# usbhub.net
KiCad netlist of a schematic drawn in EAGLE
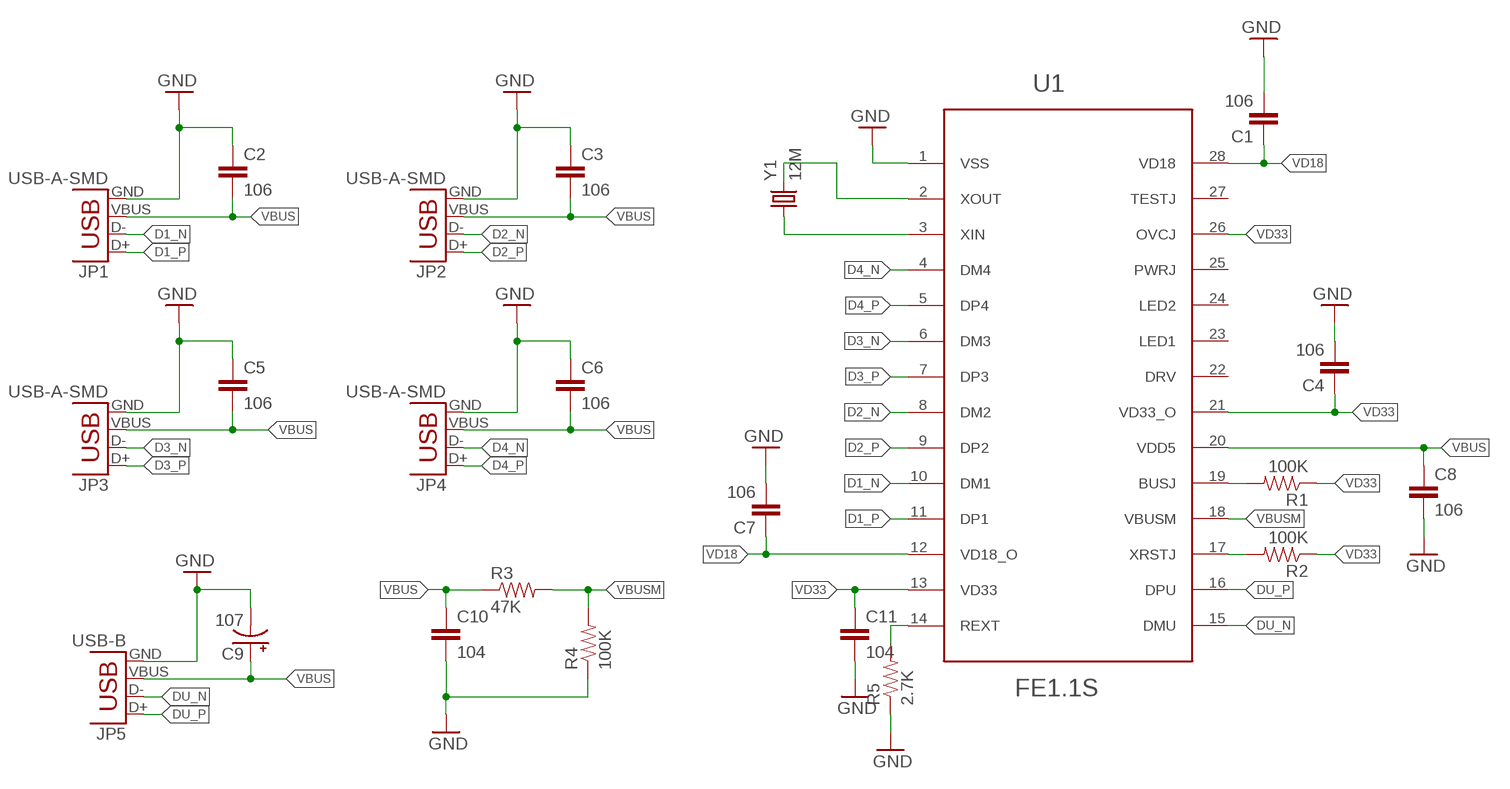
[diagram p0: schematic, sheet 1]

(export (version "E")
  (design (tool "Eeschema 10.0.6"))
  (components
    (comp (ref "C1")
      (value "106")
      (footprint "eagle-import:0603-CAP")
      (libsource (lib "eagle-import") (part "CAP0603-CAP"))
    )
    (comp (ref "C2")
      (value "106")
      (footprint "eagle-import:0603-CAP")
      (libsource (lib "eagle-import") (part "z_jlc_smt_CAP0603-CAP"))
    )
    (comp (ref "C3")
      (value "106")
      (footprint "eagle-import:0603-CAP")
      (libsource (lib "eagle-import") (part "z_jlc_smt_CAP0603-CAP"))
    )
    (comp (ref "C4")
      (value "106")
      (footprint "eagle-import:0603-CAP")
      (libsource (lib "eagle-import") (part "CAP0603-CAP"))
    )
    (comp (ref "C5")
      (value "106")
      (footprint "eagle-import:0603-CAP")
      (libsource (lib "eagle-import") (part "z_jlc_smt_CAP0603-CAP"))
    )
    (comp (ref "C6")
      (value "106")
      (footprint "eagle-import:0603-CAP")
      (libsource (lib "eagle-import") (part "z_jlc_smt_CAP0603-CAP"))
    )
    (comp (ref "C7")
      (value "106")
      (footprint "eagle-import:0603-CAP")
      (libsource (lib "eagle-import") (part "CAP0603-CAP"))
    )
    (comp (ref "C8")
      (value "106")
      (footprint "eagle-import:0603-CAP")
      (libsource (lib "eagle-import") (part "CAP0603-CAP"))
    )
    (comp (ref "C9")
      (value "107")
      (footprint "eagle-import:EIA3528-KIT")
      (libsource (lib "eagle-import") (part "CAP_POL3528-KIT"))
    )
    (comp (ref "C10")
      (value "104")
      (footprint "eagle-import:0603-CAP")
      (libsource (lib "eagle-import") (part "z_jlc_smt_CAP0603-CAP"))
    )
    (comp (ref "C11")
      (value "104")
      (footprint "eagle-import:0603-CAP")
      (libsource (lib "eagle-import") (part "CAP0603-CAP"))
    )
    (comp (ref "JP1")
      (value "USB-A-SMD")
      (footprint "eagle-import:USB-A-S-NOSILK-FEMALE")
      (libsource (lib "eagle-import") (part "USB-A-SMD"))
    )
    (comp (ref "JP2")
      (value "USB-A-SMD")
      (footprint "eagle-import:USB-A-S-NOSILK-FEMALE")
      (libsource (lib "eagle-import") (part "USB-A-SMD"))
    )
    (comp (ref "JP3")
      (value "USB-A-SMD")
      (footprint "eagle-import:USB-A-S-NOSILK-FEMALE")
      (libsource (lib "eagle-import") (part "USB-A-SMD"))
    )
    (comp (ref "JP4")
      (value "USB-A-SMD")
      (footprint "eagle-import:USB-A-S-NOSILK-FEMALE")
      (libsource (lib "eagle-import") (part "USB-A-SMD"))
    )
    (comp (ref "JP5")
      (value "USB-B")
      (footprint "eagle-import:USB-B-PTH")
      (libsource (lib "eagle-import") (part "USBPTH"))
    )
    (comp (ref "R1")
      (value "100K")
      (footprint "eagle-import:0603-RES")
      (libsource (lib "eagle-import") (part "RESISTOR0603-RES"))
    )
    (comp (ref "R2")
      (value "100K")
      (footprint "eagle-import:0603-RES")
      (libsource (lib "eagle-import") (part "RESISTOR0603-RES"))
    )
    (comp (ref "R3")
      (value "47K")
      (footprint "eagle-import:0603-RES")
      (libsource (lib "eagle-import") (part "RESISTOR0603-RES"))
    )
    (comp (ref "R4")
      (value "100K")
      (footprint "eagle-import:0603-RES")
      (libsource (lib "eagle-import") (part "RESISTOR0603-RES"))
    )
    (comp (ref "R5")
      (value "2.7K")
      (footprint "eagle-import:0603-RES")
      (libsource (lib "eagle-import") (part "RESISTOR0603-RES"))
    )
    (comp (ref "U1")
      (value "FE1.1S")
      (footprint "eagle-import:SSOP28-39")
      (libsource (lib "eagle-import") (part "FE1.1S"))
    )
    (comp (ref "Y1")
      (value "12M")
      (footprint "eagle-import:HC49US")
      (libsource (lib "eagle-import") (part "CRYSTAL2HC49US"))
    )
  )
  (nets
    (net (code "1") (name "D1_N") (class "Default")
      (node (ref "JP1") (pin "D-") (pinfunction "D-_D-") (pintype "bidirectional"))
      (node (ref "U1") (pin "10") (pinfunction "DM1_10") (pintype "bidirectional"))
    )
    (net (code "2") (name "D1_P") (class "Default")
      (node (ref "JP1") (pin "D+") (pinfunction "D+_D+") (pintype "bidirectional"))
      (node (ref "U1") (pin "11") (pinfunction "DP1_11") (pintype "bidirectional"))
    )
    (net (code "3") (name "D2_N") (class "Default")
      (node (ref "JP2") (pin "D-") (pinfunction "D-_D-") (pintype "bidirectional"))
      (node (ref "U1") (pin "8") (pinfunction "DM2_8") (pintype "bidirectional"))
    )
    (net (code "4") (name "D2_P") (class "Default")
      (node (ref "JP2") (pin "D+") (pinfunction "D+_D+") (pintype "bidirectional"))
      (node (ref "U1") (pin "9") (pinfunction "DP2_9") (pintype "bidirectional"))
    )
    (net (code "5") (name "D3_N") (class "Default")
      (node (ref "JP3") (pin "D-") (pinfunction "D-_D-") (pintype "bidirectional"))
      (node (ref "U1") (pin "6") (pinfunction "DM3_6") (pintype "bidirectional"))
    )
    (net (code "6") (name "D3_P") (class "Default")
      (node (ref "JP3") (pin "D+") (pinfunction "D+_D+") (pintype "bidirectional"))
      (node (ref "U1") (pin "7") (pinfunction "DP3_7") (pintype "bidirectional"))
    )
    (net (code "7") (name "D4_N") (class "Default")
      (node (ref "JP4") (pin "D-") (pinfunction "D-_D-") (pintype "bidirectional"))
      (node (ref "U1") (pin "4") (pinfunction "DM4_4") (pintype "bidirectional"))
    )
    (net (code "8") (name "D4_P") (class "Default")
      (node (ref "JP4") (pin "D+") (pinfunction "D+_D+") (pintype "bidirectional"))
      (node (ref "U1") (pin "5") (pinfunction "DP4_5") (pintype "bidirectional"))
    )
    (net (code "9") (name "DU_N") (class "Default")
      (node (ref "JP5") (pin "D-") (pinfunction "D-_D-") (pintype "bidirectional"))
      (node (ref "U1") (pin "15") (pinfunction "DMU_15") (pintype "bidirectional"))
    )
    (net (code "10") (name "DU_P") (class "Default")
      (node (ref "JP5") (pin "D+") (pinfunction "D+_D+") (pintype "bidirectional"))
      (node (ref "U1") (pin "16") (pinfunction "DPU_16") (pintype "bidirectional"))
    )
    (net (code "11") (name "GND") (class "Default")
      (node (ref "C1") (pin "2") (pinfunction "2_2") (pintype "passive"))
      (node (ref "C10") (pin "2") (pinfunction "2_2") (pintype "passive"))
      (node (ref "C11") (pin "2") (pinfunction "2_2") (pintype "passive"))
      (node (ref "C2") (pin "1") (pinfunction "1_1") (pintype "passive"))
      (node (ref "C3") (pin "1") (pinfunction "1_1") (pintype "passive"))
      (node (ref "C4") (pin "2") (pinfunction "2_2") (pintype "passive"))
      (node (ref "C5") (pin "1") (pinfunction "1_1") (pintype "passive"))
      (node (ref "C6") (pin "1") (pinfunction "1_1") (pintype "passive"))
      (node (ref "C7") (pin "2") (pinfunction "2_2") (pintype "passive"))
      (node (ref "C8") (pin "2") (pinfunction "2_2") (pintype "passive"))
      (node (ref "C9") (pin "C") (pinfunction "-_C") (pintype "passive"))
      (node (ref "JP1") (pin "GND") (pinfunction "GND_GND") (pintype "bidirectional"))
      (node (ref "JP2") (pin "GND") (pinfunction "GND_GND") (pintype "bidirectional"))
      (node (ref "JP3") (pin "GND") (pinfunction "GND_GND") (pintype "bidirectional"))
      (node (ref "JP4") (pin "GND") (pinfunction "GND_GND") (pintype "bidirectional"))
      (node (ref "JP5") (pin "GND") (pinfunction "GND_GND") (pintype "bidirectional"))
      (node (ref "R4") (pin "1") (pinfunction "1_1") (pintype "passive"))
      (node (ref "R5") (pin "1") (pinfunction "1_1") (pintype "passive"))
      (node (ref "U1") (pin "1") (pinfunction "VSS_1") (pintype "bidirectional"))
    )
    (net (code "12") (name "Net-(U1-BUSJ)") (class "Default")
      (node (ref "R1") (pin "2") (pinfunction "2_2") (pintype "passive"))
      (node (ref "U1") (pin "19") (pinfunction "BUSJ_19") (pintype "bidirectional"))
    )
    (net (code "13") (name "Net-(U1-REXT)") (class "Default")
      (node (ref "R5") (pin "2") (pinfunction "2_2") (pintype "passive"))
      (node (ref "U1") (pin "14") (pinfunction "REXT_14") (pintype "bidirectional"))
    )
    (net (code "14") (name "Net-(U1-XIN)") (class "Default")
      (node (ref "U1") (pin "3") (pinfunction "XIN_3") (pintype "bidirectional"))
      (node (ref "Y1") (pin "1") (pinfunction "1_1") (pintype "passive"))
    )
    (net (code "15") (name "Net-(U1-XOUT)") (class "Default")
      (node (ref "U1") (pin "2") (pinfunction "XOUT_2") (pintype "bidirectional"))
      (node (ref "Y1") (pin "2") (pinfunction "2_2") (pintype "passive"))
    )
    (net (code "16") (name "Net-(U1-XRSTJ)") (class "Default")
      (node (ref "R2") (pin "2") (pinfunction "2_2") (pintype "passive"))
      (node (ref "U1") (pin "17") (pinfunction "XRSTJ_17") (pintype "bidirectional"))
    )
    (net (code "17") (name "VBUS") (class "Default")
      (node (ref "C10") (pin "1") (pinfunction "1_1") (pintype "passive"))
      (node (ref "C2") (pin "2") (pinfunction "2_2") (pintype "passive"))
      (node (ref "C3") (pin "2") (pinfunction "2_2") (pintype "passive"))
      (node (ref "C5") (pin "2") (pinfunction "2_2") (pintype "passive"))
      (node (ref "C6") (pin "2") (pinfunction "2_2") (pintype "passive"))
      (node (ref "C8") (pin "1") (pinfunction "1_1") (pintype "passive"))
      (node (ref "C9") (pin "A") (pinfunction "+_A") (pintype "passive"))
      (node (ref "JP1") (pin "VBUS") (pinfunction "VBUS_VBUS") (pintype "bidirectional"))
      (node (ref "JP2") (pin "VBUS") (pinfunction "VBUS_VBUS") (pintype "bidirectional"))
      (node (ref "JP3") (pin "VBUS") (pinfunction "VBUS_VBUS") (pintype "bidirectional"))
      (node (ref "JP4") (pin "VBUS") (pinfunction "VBUS_VBUS") (pintype "bidirectional"))
      (node (ref "JP5") (pin "VBUS") (pinfunction "VBUS_VBUS") (pintype "bidirectional"))
      (node (ref "R3") (pin "1") (pinfunction "1_1") (pintype "passive"))
      (node (ref "U1") (pin "20") (pinfunction "VDD5_20") (pintype "bidirectional"))
    )
    (net (code "18") (name "VBUSM") (class "Default")
      (node (ref "R3") (pin "2") (pinfunction "2_2") (pintype "passive"))
      (node (ref "R4") (pin "2") (pinfunction "2_2") (pintype "passive"))
      (node (ref "U1") (pin "18") (pinfunction "VBUSM_18") (pintype "bidirectional"))
    )
    (net (code "19") (name "VD18") (class "Default")
      (node (ref "C1") (pin "1") (pinfunction "1_1") (pintype "passive"))
      (node (ref "C7") (pin "1") (pinfunction "1_1") (pintype "passive"))
      (node (ref "U1") (pin "12") (pinfunction "VD18_O_12") (pintype "bidirectional"))
      (node (ref "U1") (pin "28") (pinfunction "VD18_28") (pintype "bidirectional"))
    )
    (net (code "20") (name "VD33") (class "Default")
      (node (ref "C11") (pin "1") (pinfunction "1_1") (pintype "passive"))
      (node (ref "C4") (pin "1") (pinfunction "1_1") (pintype "passive"))
      (node (ref "R1") (pin "1") (pinfunction "1_1") (pintype "passive"))
      (node (ref "R2") (pin "1") (pinfunction "1_1") (pintype "passive"))
      (node (ref "U1") (pin "13") (pinfunction "VD33_13") (pintype "bidirectional"))
      (node (ref "U1") (pin "21") (pinfunction "VD33_O_21") (pintype "bidirectional"))
      (node (ref "U1") (pin "26") (pinfunction "OVCJ_26") (pintype "bidirectional"))
    )
    (net (code "21") (name "unconnected-(U1-DRV-Pad22)") (class "Default")
      (node (ref "U1") (pin "22") (pinfunction "DRV_22") (pintype "bidirectional"))
    )
    (net (code "22") (name "unconnected-(U1-LED1-Pad23)") (class "Default")
      (node (ref "U1") (pin "23") (pinfunction "LED1_23") (pintype "bidirectional"))
    )
    (net (code "23") (name "unconnected-(U1-LED2-Pad24)") (class "Default")
      (node (ref "U1") (pin "24") (pinfunction "LED2_24") (pintype "bidirectional"))
    )
    (net (code "24") (name "unconnected-(U1-PWRJ-Pad25)") (class "Default")
      (node (ref "U1") (pin "25") (pinfunction "PWRJ_25") (pintype "bidirectional"))
    )
    (net (code "25") (name "unconnected-(U1-TESTJ-Pad27)") (class "Default")
      (node (ref "U1") (pin "27") (pinfunction "TESTJ_27") (pintype "bidirectional"))
    )
  )
)
